# tssop16.net
KiCad netlist of a schematic drawn in EAGLE
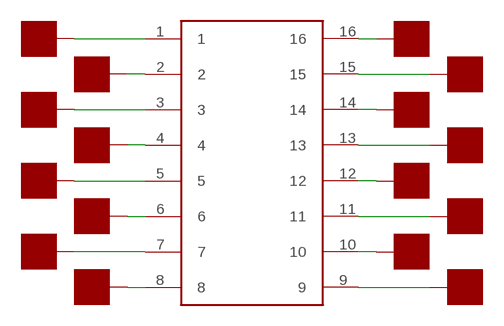
[diagram p0: schematic, sheet 1]

(export (version "E")
  (design (tool "Eeschema 10.0.6"))
  (components
    (comp (ref "IC1")
      (value "TSSOP-16")
      (footprint "eagle-import:TSSOP-16")
      (libsource (lib "eagle-import") (part "TSSOP-16"))
    )
    (comp (ref "U$1")
      (value "PAD50MIL")
      (footprint "eagle-import:PAD_50MIL")
      (libsource (lib "eagle-import") (part "PAD50MIL"))
    )
    (comp (ref "U$2")
      (value "PAD50MIL")
      (footprint "eagle-import:PAD_50MIL")
      (libsource (lib "eagle-import") (part "PAD50MIL"))
    )
    (comp (ref "U$3")
      (value "PAD50MIL")
      (footprint "eagle-import:PAD_50MIL")
      (libsource (lib "eagle-import") (part "PAD50MIL"))
    )
    (comp (ref "U$4")
      (value "PAD50MIL")
      (footprint "eagle-import:PAD_50MIL")
      (libsource (lib "eagle-import") (part "PAD50MIL"))
    )
    (comp (ref "U$5")
      (value "PAD50MIL")
      (footprint "eagle-import:PAD_50MIL")
      (libsource (lib "eagle-import") (part "PAD50MIL"))
    )
    (comp (ref "U$6")
      (value "PAD50MIL")
      (footprint "eagle-import:PAD_50MIL")
      (libsource (lib "eagle-import") (part "PAD50MIL"))
    )
    (comp (ref "U$7")
      (value "PAD50MIL")
      (footprint "eagle-import:PAD_50MIL")
      (libsource (lib "eagle-import") (part "PAD50MIL"))
    )
    (comp (ref "U$8")
      (value "PAD50MIL")
      (footprint "eagle-import:PAD_50MIL")
      (libsource (lib "eagle-import") (part "PAD50MIL"))
    )
    (comp (ref "U$9")
      (value "PAD50MIL")
      (footprint "eagle-import:PAD_50MIL")
      (libsource (lib "eagle-import") (part "PAD50MIL"))
    )
    (comp (ref "U$10")
      (value "PAD50MIL")
      (footprint "eagle-import:PAD_50MIL")
      (libsource (lib "eagle-import") (part "PAD50MIL"))
    )
    (comp (ref "U$11")
      (value "PAD50MIL")
      (footprint "eagle-import:PAD_50MIL")
      (libsource (lib "eagle-import") (part "PAD50MIL"))
    )
    (comp (ref "U$12")
      (value "PAD50MIL")
      (footprint "eagle-import:PAD_50MIL")
      (libsource (lib "eagle-import") (part "PAD50MIL"))
    )
    (comp (ref "U$13")
      (value "PAD50MIL")
      (footprint "eagle-import:PAD_50MIL")
      (libsource (lib "eagle-import") (part "PAD50MIL"))
    )
    (comp (ref "U$14")
      (value "PAD50MIL")
      (footprint "eagle-import:PAD_50MIL")
      (libsource (lib "eagle-import") (part "PAD50MIL"))
    )
    (comp (ref "U$15")
      (value "PAD50MIL")
      (footprint "eagle-import:PAD_50MIL")
      (libsource (lib "eagle-import") (part "PAD50MIL"))
    )
    (comp (ref "U$16")
      (value "PAD50MIL")
      (footprint "eagle-import:PAD_50MIL")
      (libsource (lib "eagle-import") (part "PAD50MIL"))
    )
  )
  (nets
    (net (code "1") (name "Net-(IC1-Pad1)") (class "Default")
      (node (ref "IC1") (pin "1") (pinfunction "1_1") (pintype "bidirectional"))
      (node (ref "U$16") (pin "P$1") (pinfunction "P$1_P$1") (pintype "bidirectional"))
    )
    (net (code "2") (name "Net-(IC1-Pad2)") (class "Default")
      (node (ref "IC1") (pin "2") (pinfunction "2_2") (pintype "bidirectional"))
      (node (ref "U$15") (pin "P$1") (pinfunction "P$1_P$1") (pintype "bidirectional"))
    )
    (net (code "3") (name "Net-(IC1-Pad3)") (class "Default")
      (node (ref "IC1") (pin "3") (pinfunction "3_3") (pintype "bidirectional"))
      (node (ref "U$14") (pin "P$1") (pinfunction "P$1_P$1") (pintype "bidirectional"))
    )
    (net (code "4") (name "Net-(IC1-Pad4)") (class "Default")
      (node (ref "IC1") (pin "4") (pinfunction "4_4") (pintype "bidirectional"))
      (node (ref "U$13") (pin "P$1") (pinfunction "P$1_P$1") (pintype "bidirectional"))
    )
    (net (code "5") (name "Net-(IC1-Pad5)") (class "Default")
      (node (ref "IC1") (pin "5") (pinfunction "5_5") (pintype "bidirectional"))
      (node (ref "U$12") (pin "P$1") (pinfunction "P$1_P$1") (pintype "bidirectional"))
    )
    (net (code "6") (name "Net-(IC1-Pad6)") (class "Default")
      (node (ref "IC1") (pin "6") (pinfunction "6_6") (pintype "bidirectional"))
      (node (ref "U$11") (pin "P$1") (pinfunction "P$1_P$1") (pintype "bidirectional"))
    )
    (net (code "7") (name "Net-(IC1-Pad7)") (class "Default")
      (node (ref "IC1") (pin "7") (pinfunction "7_7") (pintype "bidirectional"))
      (node (ref "U$10") (pin "P$1") (pinfunction "P$1_P$1") (pintype "bidirectional"))
    )
    (net (code "8") (name "Net-(IC1-Pad8)") (class "Default")
      (node (ref "IC1") (pin "8") (pinfunction "8_8") (pintype "bidirectional"))
      (node (ref "U$9") (pin "P$1") (pinfunction "P$1_P$1") (pintype "bidirectional"))
    )
    (net (code "9") (name "Net-(IC1-Pad9)") (class "Default")
      (node (ref "IC1") (pin "9") (pinfunction "9_9") (pintype "bidirectional"))
      (node (ref "U$8") (pin "P$1") (pinfunction "P$1_P$1") (pintype "bidirectional"))
    )
    (net (code "10") (name "Net-(IC1-Pad10)") (class "Default")
      (node (ref "IC1") (pin "10") (pinfunction "10_10") (pintype "bidirectional"))
      (node (ref "U$7") (pin "P$1") (pinfunction "P$1_P$1") (pintype "bidirectional"))
    )
    (net (code "11") (name "Net-(IC1-Pad11)") (class "Default")
      (node (ref "IC1") (pin "11") (pinfunction "11_11") (pintype "bidirectional"))
      (node (ref "U$6") (pin "P$1") (pinfunction "P$1_P$1") (pintype "bidirectional"))
    )
    (net (code "12") (name "Net-(IC1-Pad12)") (class "Default")
      (node (ref "IC1") (pin "12") (pinfunction "12_12") (pintype "bidirectional"))
      (node (ref "U$5") (pin "P$1") (pinfunction "P$1_P$1") (pintype "bidirectional"))
    )
    (net (code "13") (name "Net-(IC1-Pad13)") (class "Default")
      (node (ref "IC1") (pin "13") (pinfunction "13_13") (pintype "bidirectional"))
      (node (ref "U$4") (pin "P$1") (pinfunction "P$1_P$1") (pintype "bidirectional"))
    )
    (net (code "14") (name "Net-(IC1-Pad14)") (class "Default")
      (node (ref "IC1") (pin "14") (pinfunction "14_14") (pintype "bidirectional"))
      (node (ref "U$3") (pin "P$1") (pinfunction "P$1_P$1") (pintype "bidirectional"))
    )
    (net (code "15") (name "Net-(IC1-Pad15)") (class "Default")
      (node (ref "IC1") (pin "15") (pinfunction "15_15") (pintype "bidirectional"))
      (node (ref "U$2") (pin "P$1") (pinfunction "P$1_P$1") (pintype "bidirectional"))
    )
    (net (code "16") (name "Net-(IC1-Pad16)") (class "Default")
      (node (ref "IC1") (pin "16") (pinfunction "16_16") (pintype "bidirectional"))
      (node (ref "U$1") (pin "P$1") (pinfunction "P$1_P$1") (pintype "bidirectional"))
    )
  )
)
